# sram_v2.net
KiCad netlist of a schematic drawn in EAGLE
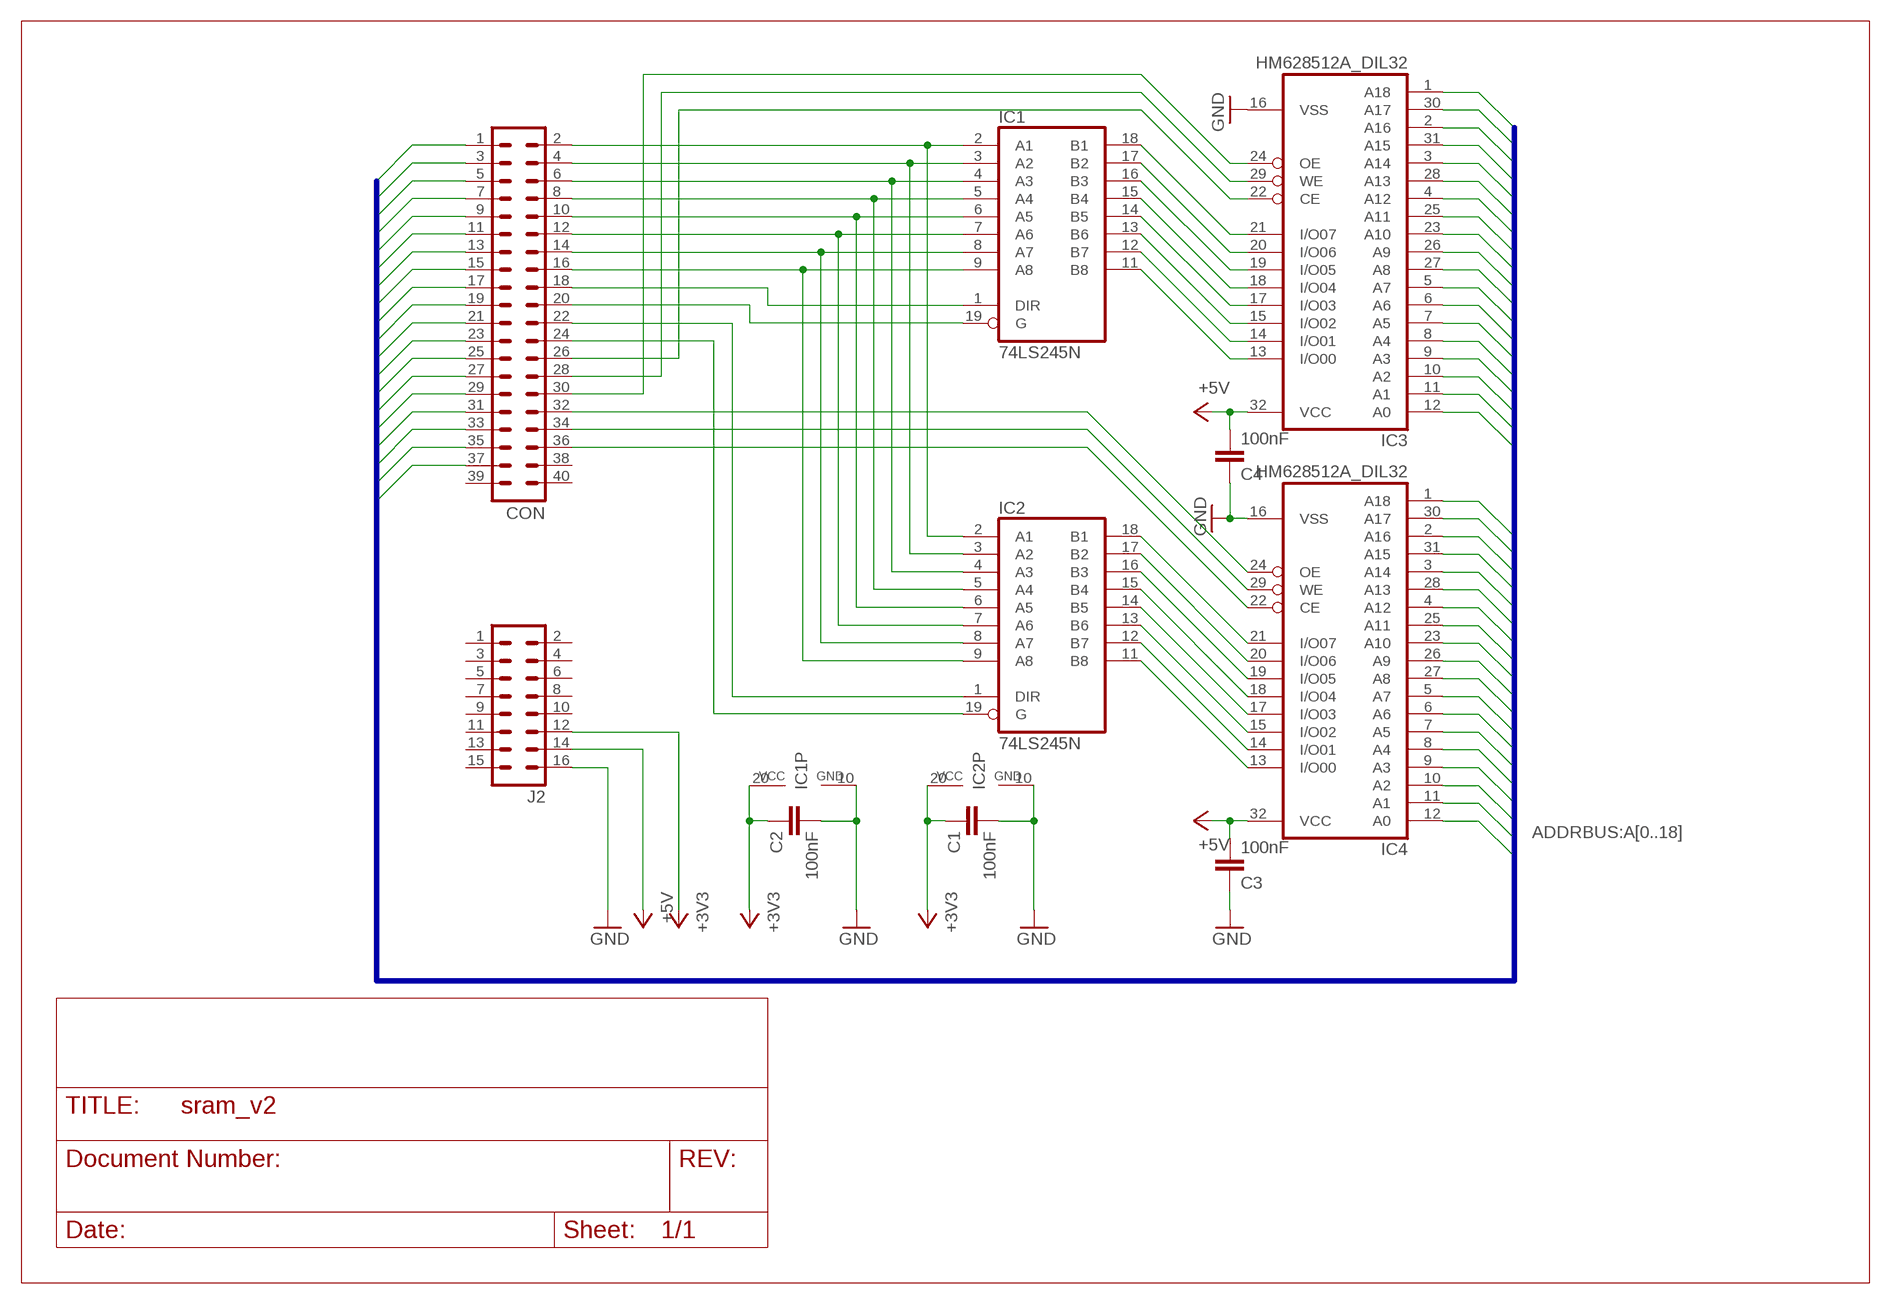
[diagram p0: schematic, sheet 1]

(export (version "E")
  (design (tool "Eeschema 10.0.6"))
  (components
    (comp (ref "C1")
      (value "100nF")
      (footprint "eagle-import:C050-030X075")
      (libsource (lib "eagle-import") (part "C-EU050-030X075"))
    )
    (comp (ref "C2")
      (value "100nF")
      (footprint "eagle-import:C050-030X075")
      (libsource (lib "eagle-import") (part "C-EU050-030X075"))
    )
    (comp (ref "C3")
      (value "100nF")
      (footprint "eagle-import:C050-030X075")
      (libsource (lib "eagle-import") (part "C-EU050-030X075"))
    )
    (comp (ref "C4")
      (value "100nF")
      (footprint "eagle-import:C050-030X075")
      (libsource (lib "eagle-import") (part "C-EU050-030X075"))
    )
    (comp (ref "CON")
      (value "ML40")
      (footprint "eagle-import:ML40")
      (libsource (lib "eagle-import") (part "ML40"))
    )
    (comp (ref "IC1")
      (value "74LS245N")
      (footprint "eagle-import:DIL20")
      (libsource (lib "eagle-import") (part "74245NLS"))
    )
    (comp (ref "IC2")
      (value "74LS245N")
      (footprint "eagle-import:DIL20")
      (libsource (lib "eagle-import") (part "74245NLS"))
    )
    (comp (ref "IC3")
      (value "HM628512A_DIL32")
      (footprint "eagle-import:DIL32")
      (libsource (lib "eagle-import") (part "HM628512A_DIL32"))
    )
    (comp (ref "IC4")
      (value "HM628512A_DIL32")
      (footprint "eagle-import:DIL32")
      (libsource (lib "eagle-import") (part "HM628512A_DIL32"))
    )
    (comp (ref "J2")
      (value "ML16")
      (footprint "eagle-import:ML16")
      (libsource (lib "eagle-import") (part "ML16"))
    )
  )
  (nets
    (net (code "20") (name "+3V3") (class "Default")
      (node (ref "C1") (pin "1") (pinfunction "1_1") (pintype "passive"))
      (node (ref "C2") (pin "1") (pinfunction "1_1") (pintype "passive"))
      (node (ref "IC1") (pin "20") (pinfunction "VCC_20") (pintype "power_in"))
      (node (ref "IC2") (pin "20") (pinfunction "VCC_20") (pintype "power_in"))
      (node (ref "J2") (pin "12") (pinfunction "12_12") (pintype "passive"))
    )
    (net (code "21") (name "+5V") (class "Default")
      (node (ref "C3") (pin "2") (pinfunction "2_2") (pintype "passive"))
      (node (ref "C4") (pin "2") (pinfunction "2_2") (pintype "passive"))
      (node (ref "IC3") (pin "32") (pinfunction "VCC_32") (pintype "power_in"))
      (node (ref "IC4") (pin "32") (pinfunction "VCC_32") (pintype "power_in"))
      (node (ref "J2") (pin "14") (pinfunction "14_14") (pintype "passive"))
    )
    (net (code "22") (name "/A0") (class "Default")
      (node (ref "CON") (pin "1") (pinfunction "1_1") (pintype "passive"))
      (node (ref "IC3") (pin "12") (pinfunction "A0_12") (pintype "input"))
      (node (ref "IC4") (pin "12") (pinfunction "A0_12") (pintype "input"))
    )
    (net (code "23") (name "/A1") (class "Default")
      (node (ref "CON") (pin "3") (pinfunction "3_3") (pintype "passive"))
      (node (ref "IC3") (pin "11") (pinfunction "A1_11") (pintype "input"))
      (node (ref "IC4") (pin "11") (pinfunction "A1_11") (pintype "input"))
    )
    (net (code "24") (name "/A2") (class "Default")
      (node (ref "CON") (pin "5") (pinfunction "5_5") (pintype "passive"))
      (node (ref "IC3") (pin "10") (pinfunction "A2_10") (pintype "input"))
      (node (ref "IC4") (pin "10") (pinfunction "A2_10") (pintype "input"))
    )
    (net (code "25") (name "/A3") (class "Default")
      (node (ref "CON") (pin "7") (pinfunction "7_7") (pintype "passive"))
      (node (ref "IC3") (pin "9") (pinfunction "A3_9") (pintype "input"))
      (node (ref "IC4") (pin "9") (pinfunction "A3_9") (pintype "input"))
    )
    (net (code "26") (name "/A4") (class "Default")
      (node (ref "CON") (pin "9") (pinfunction "9_9") (pintype "passive"))
      (node (ref "IC3") (pin "8") (pinfunction "A4_8") (pintype "input"))
      (node (ref "IC4") (pin "8") (pinfunction "A4_8") (pintype "input"))
    )
    (net (code "27") (name "/A5") (class "Default")
      (node (ref "CON") (pin "11") (pinfunction "11_11") (pintype "passive"))
      (node (ref "IC3") (pin "7") (pinfunction "A5_7") (pintype "input"))
      (node (ref "IC4") (pin "7") (pinfunction "A5_7") (pintype "input"))
    )
    (net (code "28") (name "/A6") (class "Default")
      (node (ref "CON") (pin "13") (pinfunction "13_13") (pintype "passive"))
      (node (ref "IC3") (pin "6") (pinfunction "A6_6") (pintype "input"))
      (node (ref "IC4") (pin "6") (pinfunction "A6_6") (pintype "input"))
    )
    (net (code "29") (name "/A7") (class "Default")
      (node (ref "CON") (pin "15") (pinfunction "15_15") (pintype "passive"))
      (node (ref "IC3") (pin "5") (pinfunction "A7_5") (pintype "input"))
      (node (ref "IC4") (pin "5") (pinfunction "A7_5") (pintype "input"))
    )
    (net (code "30") (name "/A8") (class "Default")
      (node (ref "CON") (pin "17") (pinfunction "17_17") (pintype "passive"))
      (node (ref "IC3") (pin "27") (pinfunction "A8_27") (pintype "input"))
      (node (ref "IC4") (pin "27") (pinfunction "A8_27") (pintype "input"))
    )
    (net (code "31") (name "/A9") (class "Default")
      (node (ref "CON") (pin "19") (pinfunction "19_19") (pintype "passive"))
      (node (ref "IC3") (pin "26") (pinfunction "A9_26") (pintype "input"))
      (node (ref "IC4") (pin "26") (pinfunction "A9_26") (pintype "input"))
    )
    (net (code "32") (name "/A10") (class "Default")
      (node (ref "CON") (pin "21") (pinfunction "21_21") (pintype "passive"))
      (node (ref "IC3") (pin "23") (pinfunction "A10_23") (pintype "input"))
      (node (ref "IC4") (pin "23") (pinfunction "A10_23") (pintype "input"))
    )
    (net (code "33") (name "/A11") (class "Default")
      (node (ref "CON") (pin "23") (pinfunction "23_23") (pintype "passive"))
      (node (ref "IC3") (pin "25") (pinfunction "A11_25") (pintype "input"))
      (node (ref "IC4") (pin "25") (pinfunction "A11_25") (pintype "input"))
    )
    (net (code "34") (name "/A12") (class "Default")
      (node (ref "CON") (pin "25") (pinfunction "25_25") (pintype "passive"))
      (node (ref "IC3") (pin "4") (pinfunction "A12_4") (pintype "input"))
      (node (ref "IC4") (pin "4") (pinfunction "A12_4") (pintype "input"))
    )
    (net (code "35") (name "/A13") (class "Default")
      (node (ref "CON") (pin "27") (pinfunction "27_27") (pintype "passive"))
      (node (ref "IC3") (pin "28") (pinfunction "A13_28") (pintype "input"))
      (node (ref "IC4") (pin "28") (pinfunction "A13_28") (pintype "input"))
    )
    (net (code "36") (name "/A14") (class "Default")
      (node (ref "CON") (pin "29") (pinfunction "29_29") (pintype "passive"))
      (node (ref "IC3") (pin "3") (pinfunction "A14_3") (pintype "input"))
      (node (ref "IC4") (pin "3") (pinfunction "A14_3") (pintype "input"))
    )
    (net (code "37") (name "/A15") (class "Default")
      (node (ref "CON") (pin "31") (pinfunction "31_31") (pintype "passive"))
      (node (ref "IC3") (pin "31") (pinfunction "A15_31") (pintype "input"))
      (node (ref "IC4") (pin "31") (pinfunction "A15_31") (pintype "input"))
    )
    (net (code "38") (name "/A16") (class "Default")
      (node (ref "CON") (pin "33") (pinfunction "33_33") (pintype "passive"))
      (node (ref "IC3") (pin "2") (pinfunction "A16_2") (pintype "input"))
      (node (ref "IC4") (pin "2") (pinfunction "A16_2") (pintype "input"))
    )
    (net (code "39") (name "/A17") (class "Default")
      (node (ref "CON") (pin "35") (pinfunction "35_35") (pintype "passive"))
      (node (ref "IC3") (pin "30") (pinfunction "A17_30") (pintype "input"))
      (node (ref "IC4") (pin "30") (pinfunction "A17_30") (pintype "input"))
    )
    (net (code "40") (name "/A18") (class "Default")
      (node (ref "CON") (pin "37") (pinfunction "37_37") (pintype "passive"))
      (node (ref "IC3") (pin "1") (pinfunction "A18_1") (pintype "input"))
      (node (ref "IC4") (pin "1") (pinfunction "A18_1") (pintype "input"))
    )
    (net (code "42") (name "GND") (class "Default")
      (node (ref "C1") (pin "2") (pinfunction "2_2") (pintype "passive"))
      (node (ref "C2") (pin "2") (pinfunction "2_2") (pintype "passive"))
      (node (ref "C3") (pin "1") (pinfunction "1_1") (pintype "passive"))
      (node (ref "C4") (pin "1") (pinfunction "1_1") (pintype "passive"))
      (node (ref "IC1") (pin "10") (pinfunction "GND_10") (pintype "power_in"))
      (node (ref "IC2") (pin "10") (pinfunction "GND_10") (pintype "power_in"))
      (node (ref "IC3") (pin "16") (pinfunction "VSS_16") (pintype "power_in"))
      (node (ref "IC4") (pin "16") (pinfunction "VSS_16") (pintype "power_in"))
      (node (ref "J2") (pin "16") (pinfunction "16_16") (pintype "passive"))
    )
    (net (code "43") (name "Net-(IC1A-A1)") (class "Default")
      (node (ref "CON") (pin "2") (pinfunction "2_2") (pintype "passive"))
      (node (ref "IC1") (pin "2") (pinfunction "A1_2") (pintype "bidirectional"))
      (node (ref "IC2") (pin "2") (pinfunction "A1_2") (pintype "bidirectional"))
    )
    (net (code "44") (name "Net-(IC1A-A2)") (class "Default")
      (node (ref "CON") (pin "4") (pinfunction "4_4") (pintype "passive"))
      (node (ref "IC1") (pin "3") (pinfunction "A2_3") (pintype "bidirectional"))
      (node (ref "IC2") (pin "3") (pinfunction "A2_3") (pintype "bidirectional"))
    )
    (net (code "45") (name "Net-(IC1A-A3)") (class "Default")
      (node (ref "CON") (pin "6") (pinfunction "6_6") (pintype "passive"))
      (node (ref "IC1") (pin "4") (pinfunction "A3_4") (pintype "bidirectional"))
      (node (ref "IC2") (pin "4") (pinfunction "A3_4") (pintype "bidirectional"))
    )
    (net (code "46") (name "Net-(IC1A-A4)") (class "Default")
      (node (ref "CON") (pin "8") (pinfunction "8_8") (pintype "passive"))
      (node (ref "IC1") (pin "5") (pinfunction "A4_5") (pintype "bidirectional"))
      (node (ref "IC2") (pin "5") (pinfunction "A4_5") (pintype "bidirectional"))
    )
    (net (code "47") (name "Net-(IC1A-A5)") (class "Default")
      (node (ref "CON") (pin "10") (pinfunction "10_10") (pintype "passive"))
      (node (ref "IC1") (pin "6") (pinfunction "A5_6") (pintype "bidirectional"))
      (node (ref "IC2") (pin "6") (pinfunction "A5_6") (pintype "bidirectional"))
    )
    (net (code "48") (name "Net-(IC1A-A6)") (class "Default")
      (node (ref "CON") (pin "12") (pinfunction "12_12") (pintype "passive"))
      (node (ref "IC1") (pin "7") (pinfunction "A6_7") (pintype "bidirectional"))
      (node (ref "IC2") (pin "7") (pinfunction "A6_7") (pintype "bidirectional"))
    )
    (net (code "49") (name "Net-(IC1A-A7)") (class "Default")
      (node (ref "CON") (pin "14") (pinfunction "14_14") (pintype "passive"))
      (node (ref "IC1") (pin "8") (pinfunction "A7_8") (pintype "bidirectional"))
      (node (ref "IC2") (pin "8") (pinfunction "A7_8") (pintype "bidirectional"))
    )
    (net (code "50") (name "Net-(IC1A-A8)") (class "Default")
      (node (ref "CON") (pin "16") (pinfunction "16_16") (pintype "passive"))
      (node (ref "IC1") (pin "9") (pinfunction "A8_9") (pintype "bidirectional"))
      (node (ref "IC2") (pin "9") (pinfunction "A8_9") (pintype "bidirectional"))
    )
    (net (code "51") (name "Net-(IC1A-B1)") (class "Default")
      (node (ref "IC1") (pin "18") (pinfunction "B1_18") (pintype "bidirectional"))
      (node (ref "IC3") (pin "21") (pinfunction "I/O07_21") (pintype "bidirectional"))
    )
    (net (code "52") (name "Net-(IC1A-B2)") (class "Default")
      (node (ref "IC1") (pin "17") (pinfunction "B2_17") (pintype "bidirectional"))
      (node (ref "IC3") (pin "20") (pinfunction "I/O06_20") (pintype "bidirectional"))
    )
    (net (code "53") (name "Net-(IC1A-B3)") (class "Default")
      (node (ref "IC1") (pin "16") (pinfunction "B3_16") (pintype "bidirectional"))
      (node (ref "IC3") (pin "19") (pinfunction "I/O05_19") (pintype "bidirectional"))
    )
    (net (code "54") (name "Net-(IC1A-B4)") (class "Default")
      (node (ref "IC1") (pin "15") (pinfunction "B4_15") (pintype "bidirectional"))
      (node (ref "IC3") (pin "18") (pinfunction "I/O04_18") (pintype "bidirectional"))
    )
    (net (code "55") (name "Net-(IC1A-B5)") (class "Default")
      (node (ref "IC1") (pin "14") (pinfunction "B5_14") (pintype "bidirectional"))
      (node (ref "IC3") (pin "17") (pinfunction "I/O03_17") (pintype "bidirectional"))
    )
    (net (code "56") (name "Net-(IC1A-B6)") (class "Default")
      (node (ref "IC1") (pin "13") (pinfunction "B6_13") (pintype "bidirectional"))
      (node (ref "IC3") (pin "15") (pinfunction "I/O02_15") (pintype "bidirectional"))
    )
    (net (code "57") (name "Net-(IC1A-B7)") (class "Default")
      (node (ref "IC1") (pin "12") (pinfunction "B7_12") (pintype "bidirectional"))
      (node (ref "IC3") (pin "14") (pinfunction "I/O01_14") (pintype "bidirectional"))
    )
    (net (code "58") (name "Net-(IC1A-B8)") (class "Default")
      (node (ref "IC1") (pin "11") (pinfunction "B8_11") (pintype "bidirectional"))
      (node (ref "IC3") (pin "13") (pinfunction "I/O00_13") (pintype "bidirectional"))
    )
    (net (code "59") (name "Net-(IC1A-DIR)") (class "Default")
      (node (ref "CON") (pin "18") (pinfunction "18_18") (pintype "passive"))
      (node (ref "IC1") (pin "1") (pinfunction "DIR_1") (pintype "input"))
    )
    (net (code "60") (name "Net-(IC1A-G)") (class "Default")
      (node (ref "CON") (pin "20") (pinfunction "20_20") (pintype "passive"))
      (node (ref "IC1") (pin "19") (pinfunction "G_19") (pintype "input"))
    )
    (net (code "61") (name "Net-(IC2A-B1)") (class "Default")
      (node (ref "IC2") (pin "18") (pinfunction "B1_18") (pintype "bidirectional"))
      (node (ref "IC4") (pin "21") (pinfunction "I/O07_21") (pintype "bidirectional"))
    )
    (net (code "62") (name "Net-(IC2A-B2)") (class "Default")
      (node (ref "IC2") (pin "17") (pinfunction "B2_17") (pintype "bidirectional"))
      (node (ref "IC4") (pin "20") (pinfunction "I/O06_20") (pintype "bidirectional"))
    )
    (net (code "63") (name "Net-(IC2A-B3)") (class "Default")
      (node (ref "IC2") (pin "16") (pinfunction "B3_16") (pintype "bidirectional"))
      (node (ref "IC4") (pin "19") (pinfunction "I/O05_19") (pintype "bidirectional"))
    )
    (net (code "64") (name "Net-(IC2A-B4)") (class "Default")
      (node (ref "IC2") (pin "15") (pinfunction "B4_15") (pintype "bidirectional"))
      (node (ref "IC4") (pin "18") (pinfunction "I/O04_18") (pintype "bidirectional"))
    )
    (net (code "65") (name "Net-(IC2A-B5)") (class "Default")
      (node (ref "IC2") (pin "14") (pinfunction "B5_14") (pintype "bidirectional"))
      (node (ref "IC4") (pin "17") (pinfunction "I/O03_17") (pintype "bidirectional"))
    )
    (net (code "66") (name "Net-(IC2A-B6)") (class "Default")
      (node (ref "IC2") (pin "13") (pinfunction "B6_13") (pintype "bidirectional"))
      (node (ref "IC4") (pin "15") (pinfunction "I/O02_15") (pintype "bidirectional"))
    )
    (net (code "67") (name "Net-(IC2A-B7)") (class "Default")
      (node (ref "IC2") (pin "12") (pinfunction "B7_12") (pintype "bidirectional"))
      (node (ref "IC4") (pin "14") (pinfunction "I/O01_14") (pintype "bidirectional"))
    )
    (net (code "68") (name "Net-(IC2A-B8)") (class "Default")
      (node (ref "IC2") (pin "11") (pinfunction "B8_11") (pintype "bidirectional"))
      (node (ref "IC4") (pin "13") (pinfunction "I/O00_13") (pintype "bidirectional"))
    )
    (net (code "69") (name "Net-(IC2A-DIR)") (class "Default")
      (node (ref "CON") (pin "22") (pinfunction "22_22") (pintype "passive"))
      (node (ref "IC2") (pin "1") (pinfunction "DIR_1") (pintype "input"))
    )
    (net (code "70") (name "Net-(IC2A-G)") (class "Default")
      (node (ref "CON") (pin "24") (pinfunction "24_24") (pintype "passive"))
      (node (ref "IC2") (pin "19") (pinfunction "G_19") (pintype "input"))
    )
    (net (code "71") (name "Net-(IC3-CE)") (class "Default")
      (node (ref "CON") (pin "26") (pinfunction "26_26") (pintype "passive"))
      (node (ref "IC3") (pin "22") (pinfunction "CE_22") (pintype "input"))
    )
    (net (code "72") (name "Net-(IC3-OE)") (class "Default")
      (node (ref "CON") (pin "30") (pinfunction "30_30") (pintype "passive"))
      (node (ref "IC3") (pin "24") (pinfunction "OE_24") (pintype "input"))
    )
    (net (code "73") (name "Net-(IC3-WE)") (class "Default")
      (node (ref "CON") (pin "28") (pinfunction "28_28") (pintype "passive"))
      (node (ref "IC3") (pin "29") (pinfunction "WE_29") (pintype "input"))
    )
    (net (code "74") (name "Net-(IC4-CE)") (class "Default")
      (node (ref "CON") (pin "36") (pinfunction "36_36") (pintype "passive"))
      (node (ref "IC4") (pin "22") (pinfunction "CE_22") (pintype "input"))
    )
    (net (code "75") (name "Net-(IC4-OE)") (class "Default")
      (node (ref "CON") (pin "32") (pinfunction "32_32") (pintype "passive"))
      (node (ref "IC4") (pin "24") (pinfunction "OE_24") (pintype "input"))
    )
    (net (code "76") (name "Net-(IC4-WE)") (class "Default")
      (node (ref "CON") (pin "34") (pinfunction "34_34") (pintype "passive"))
      (node (ref "IC4") (pin "29") (pinfunction "WE_29") (pintype "input"))
    )
    (net (code "77") (name "unconnected-(CON-Pad38)") (class "Default")
      (node (ref "CON") (pin "38") (pinfunction "38_38") (pintype "passive"))
    )
    (net (code "78") (name "unconnected-(CON-Pad39)") (class "Default")
      (node (ref "CON") (pin "39") (pinfunction "39_39") (pintype "passive"))
    )
    (net (code "79") (name "unconnected-(CON-Pad40)") (class "Default")
      (node (ref "CON") (pin "40") (pinfunction "40_40") (pintype "passive"))
    )
    (net (code "80") (name "unconnected-(J2-Pad1)") (class "Default")
      (node (ref "J2") (pin "1") (pinfunction "1_1") (pintype "passive"))
    )
    (net (code "81") (name "unconnected-(J2-Pad2)") (class "Default")
      (node (ref "J2") (pin "2") (pinfunction "2_2") (pintype "passive"))
    )
    (net (code "82") (name "unconnected-(J2-Pad3)") (class "Default")
      (node (ref "J2") (pin "3") (pinfunction "3_3") (pintype "passive"))
    )
    (net (code "83") (name "unconnected-(J2-Pad4)") (class "Default")
      (node (ref "J2") (pin "4") (pinfunction "4_4") (pintype "passive"))
    )
    (net (code "84") (name "unconnected-(J2-Pad5)") (class "Default")
      (node (ref "J2") (pin "5") (pinfunction "5_5") (pintype "passive"))
    )
    (net (code "85") (name "unconnected-(J2-Pad6)") (class "Default")
      (node (ref "J2") (pin "6") (pinfunction "6_6") (pintype "passive"))
    )
    (net (code "86") (name "unconnected-(J2-Pad7)") (class "Default")
      (node (ref "J2") (pin "7") (pinfunction "7_7") (pintype "passive"))
    )
    (net (code "87") (name "unconnected-(J2-Pad8)") (class "Default")
      (node (ref "J2") (pin "8") (pinfunction "8_8") (pintype "passive"))
    )
    (net (code "88") (name "unconnected-(J2-Pad9)") (class "Default")
      (node (ref "J2") (pin "9") (pinfunction "9_9") (pintype "passive"))
    )
    (net (code "89") (name "unconnected-(J2-Pad10)") (class "Default")
      (node (ref "J2") (pin "10") (pinfunction "10_10") (pintype "passive"))
    )
    (net (code "90") (name "unconnected-(J2-Pad11)") (class "Default")
      (node (ref "J2") (pin "11") (pinfunction "11_11") (pintype "passive"))
    )
    (net (code "91") (name "unconnected-(J2-Pad13)") (class "Default")
      (node (ref "J2") (pin "13") (pinfunction "13_13") (pintype "passive"))
    )
    (net (code "92") (name "unconnected-(J2-Pad15)") (class "Default")
      (node (ref "J2") (pin "15") (pinfunction "15_15") (pintype "passive"))
    )
  )
)
